# generator_DBD.net
KiCad netlist of a schematic drawn in EAGLE
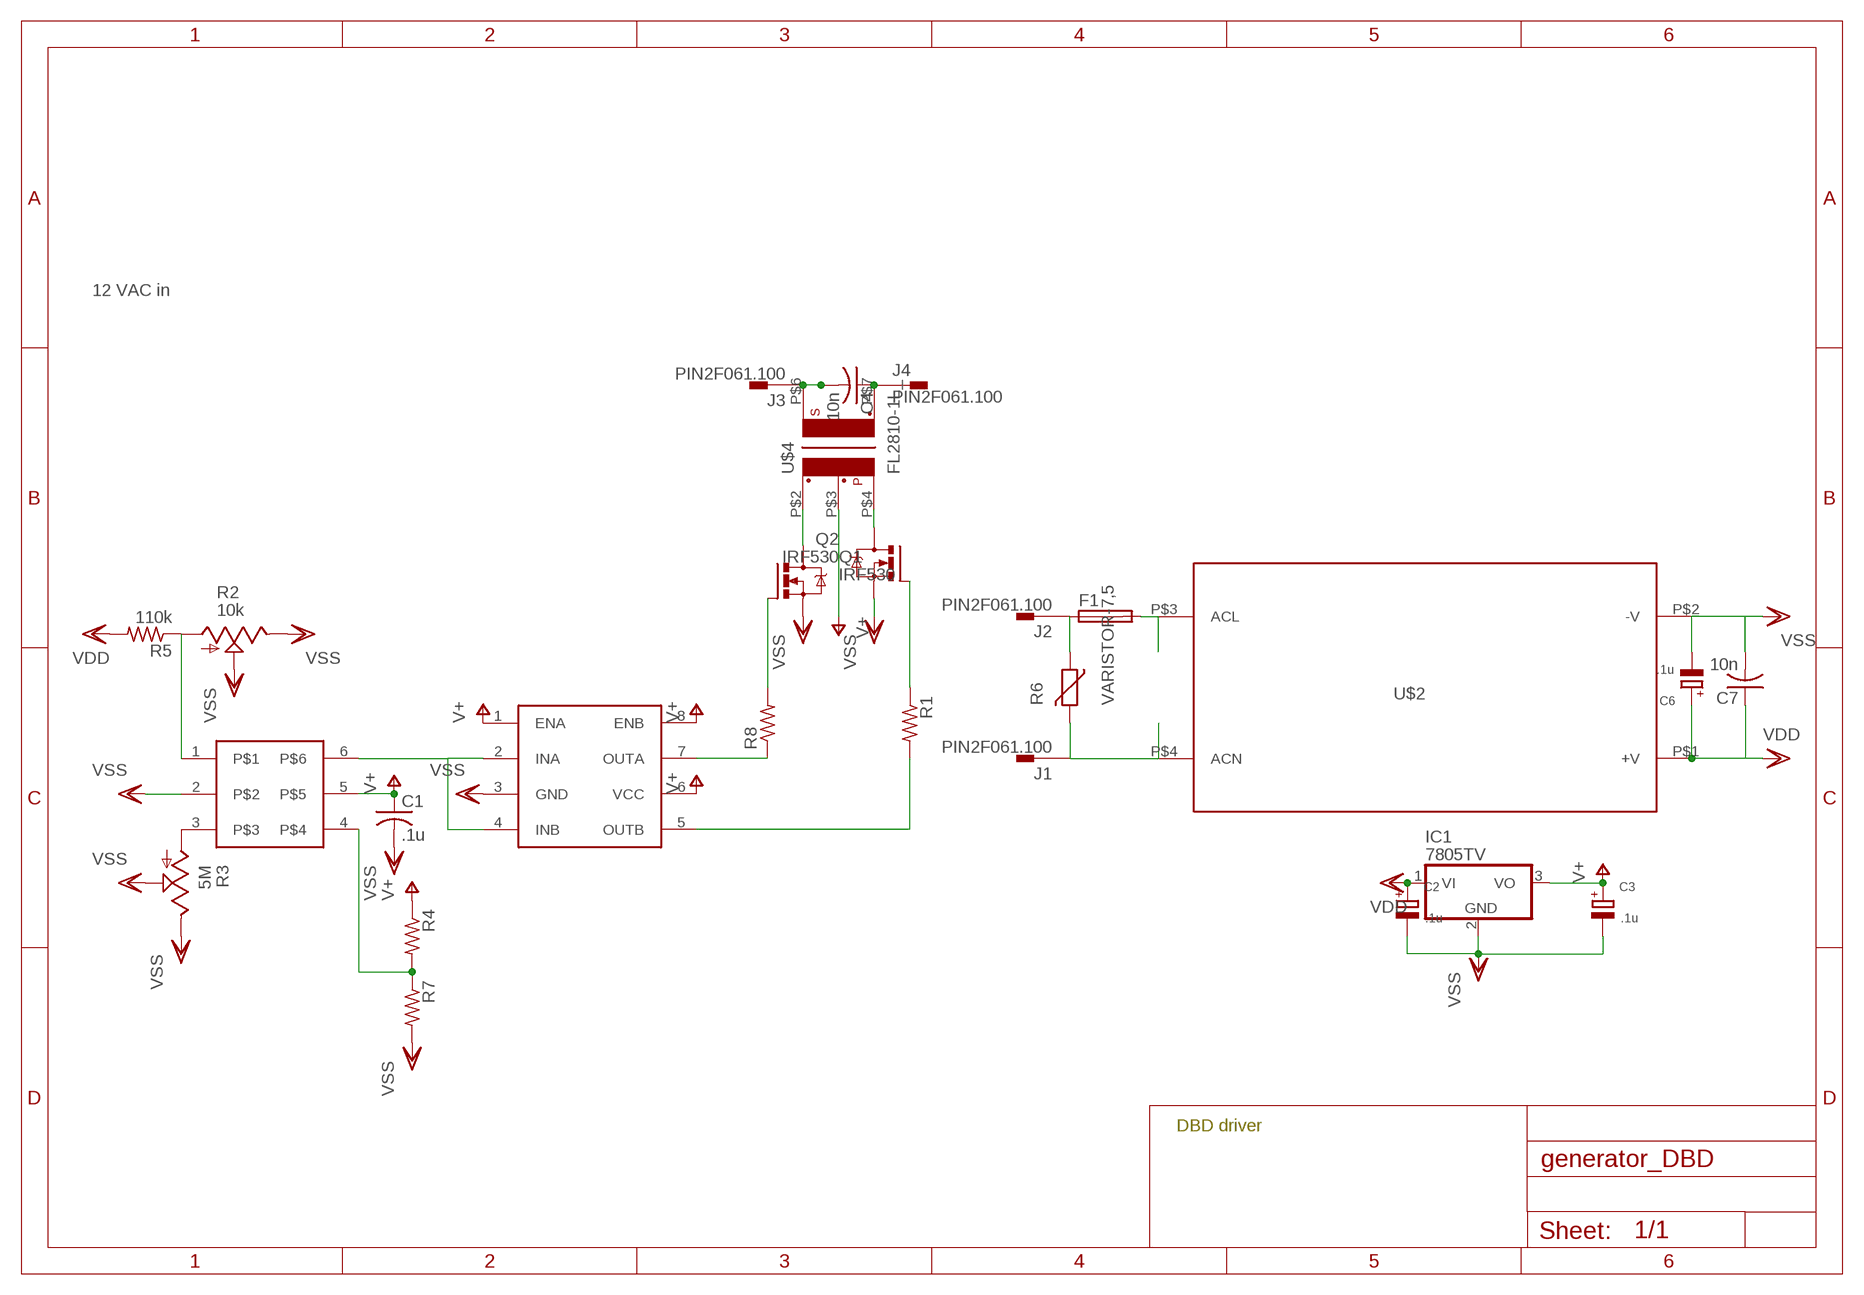
[diagram p0: schematic, sheet 1]

(export (version "E")
  (design (tool "Eeschema 10.0.6"))
  (components
    (comp (ref "C1")
      (value ".1u")
      (footprint "eagle-import:C075-042X103")
      (libsource (lib "eagle-import") (part "C-US075-042X103"))
    )
    (comp (ref "C2")
      (value ".1u")
      (footprint "eagle-import:E5-8,5")
      (libsource (lib "eagle-import") (part "CPOL-EUE5-8.5"))
    )
    (comp (ref "C3")
      (value ".1u")
      (footprint "eagle-import:E5-8,5")
      (libsource (lib "eagle-import") (part "CPOL-EUE5-8.5"))
    )
    (comp (ref "C4")
      (value "10n")
      (footprint "eagle-import:C075-042X103")
      (libsource (lib "eagle-import") (part "C-US075-042X103"))
    )
    (comp (ref "C6")
      (value ".1u")
      (footprint "eagle-import:E5-8,5")
      (libsource (lib "eagle-import") (part "CPOL-EUE5-8.5"))
    )
    (comp (ref "C7")
      (value "10n")
      (footprint "eagle-import:C075-042X103")
      (libsource (lib "eagle-import") (part "C-US075-042X103"))
    )
    (comp (ref "F1")
      (value "SH25")
      (footprint "eagle-import:SH25")
      (fields (field (name "MF") "SCHURTER") (field (name "MPN") "0031.8211"))
      (libsource (lib "eagle-import") (part "SH25"))
    )
    (comp (ref "IC1")
      (value "7805TV")
      (footprint "eagle-import:TO220V")
      (libsource (lib "eagle-import") (part "78TV05"))
    )
    (comp (ref "J1")
      (value "PIN2F061.100")
      (footprint "eagle-import:F061.100")
      (libsource (lib "eagle-import") (part "PIN2F061.100"))
    )
    (comp (ref "J2")
      (value "PIN2F061.100")
      (footprint "eagle-import:F061.100")
      (libsource (lib "eagle-import") (part "PIN2F061.100"))
    )
    (comp (ref "J3")
      (value "PIN2F061.100")
      (footprint "eagle-import:F061.100")
      (libsource (lib "eagle-import") (part "PIN2F061.100"))
    )
    (comp (ref "J4")
      (value "PIN2F061.100")
      (footprint "eagle-import:F061.100")
      (libsource (lib "eagle-import") (part "PIN2F061.100"))
    )
    (comp (ref "Q1")
      (value "IRF530")
      (footprint "eagle-import:TO220BV")
      (libsource (lib "eagle-import") (part "IRF530"))
    )
    (comp (ref "Q2")
      (value "IRF530")
      (footprint "eagle-import:TO220BV")
      (libsource (lib "eagle-import") (part "IRF530"))
    )
    (comp (ref "R1")
      (value "R-US_0207/10")
      (footprint "eagle-import:0207_10")
      (libsource (lib "eagle-import") (part "R-US_0207/10"))
    )
    (comp (ref "R2")
      (value "10k")
      (footprint "eagle-import:PT-SPIN-2")
      (libsource (lib "eagle-import") (part "TRIM_US-PT-SPIN"))
    )
    (comp (ref "R3")
      (value "5M")
      (footprint "eagle-import:PT-SPIN-2")
      (libsource (lib "eagle-import") (part "TRIM_US-PTSPIN"))
    )
    (comp (ref "R4")
      (value "R-US_0207/10")
      (footprint "eagle-import:0207_10")
      (libsource (lib "eagle-import") (part "R-US_0207/10"))
    )
    (comp (ref "R5")
      (value "110k")
      (footprint "eagle-import:0207_10")
      (libsource (lib "eagle-import") (part "R-US_0207/10"))
    )
    (comp (ref "R6")
      (value "VARISTOR-7,5")
      (footprint "eagle-import:R-7,5")
      (libsource (lib "eagle-import") (part "VARISTOR-7,5"))
    )
    (comp (ref "R7")
      (value "R-US_0207/10")
      (footprint "eagle-import:0207_10")
      (libsource (lib "eagle-import") (part "R-US_0207/10"))
    )
    (comp (ref "R8")
      (value "R-US_0207/15")
      (footprint "eagle-import:0207_15")
      (libsource (lib "eagle-import") (part "R-US_0207/15"))
    )
    (comp (ref "U$1")
      (value "UCC27425")
      (footprint "eagle-import:DIL08")
      (libsource (lib "eagle-import") (part "UCC27425"))
    )
    (comp (ref "U$2")
      (value "IRM-60-12")
      (footprint "eagle-import:IRM-60-12")
      (libsource (lib "eagle-import") (part "IRM-60-12"))
    )
    (comp (ref "U$3")
      (value "LTC6992SMD")
      (footprint "eagle-import:SOT23-6")
      (libsource (lib "eagle-import") (part "LTC6992SMD"))
    )
    (comp (ref "U$4")
      (value "FL2810-1L_")
      (footprint "eagle-import:4")
      (libsource (lib "eagle-import") (part "FL2810-1L_"))
    )
  )
  (nets
    (net (code "1") (name "Net-(F1-Pad1)") (class "Default")
      (node (ref "F1") (pin "1") (pinfunction "1_1") (pintype "passive"))
      (node (ref "J2") (pin "A1") (pinfunction "1_A1") (pintype "passive"))
      (node (ref "J2") (pin "A2") (pinfunction "1_A2") (pintype "passive"))
      (node (ref "R6") (pin "1") (pinfunction "1_1") (pintype "passive"))
    )
    (net (code "2") (name "Net-(Q1-PadG)") (class "Default")
      (node (ref "Q1") (pin "G") (pinfunction "G_G") (pintype "passive"))
      (node (ref "R8") (pin "2") (pinfunction "2_2") (pintype "passive"))
    )
    (net (code "3") (name "Net-(Q2-PadG)") (class "Default")
      (node (ref "Q2") (pin "G") (pinfunction "G_G") (pintype "passive"))
      (node (ref "R1") (pin "1") (pinfunction "1_1") (pintype "passive"))
    )
    (net (code "4") (name "Net-(U$1-INA)") (class "Default")
      (node (ref "U$1") (pin "2") (pinfunction "INA_2") (pintype "bidirectional"))
      (node (ref "U$1") (pin "4") (pinfunction "INB_4") (pintype "bidirectional"))
      (node (ref "U$3") (pin "6") (pinfunction "P$6_6") (pintype "bidirectional"))
    )
    (net (code "5") (name "Net-(U$1-OUTA)") (class "Default")
      (node (ref "R8") (pin "1") (pinfunction "1_1") (pintype "passive"))
      (node (ref "U$1") (pin "7") (pinfunction "OUTA_7") (pintype "bidirectional"))
    )
    (net (code "6") (name "Net-(U$1-OUTB)") (class "Default")
      (node (ref "R1") (pin "2") (pinfunction "2_2") (pintype "passive"))
      (node (ref "U$1") (pin "5") (pinfunction "OUTB_5") (pintype "bidirectional"))
    )
    (net (code "7") (name "Net-(U$2-ACL)") (class "Default")
      (node (ref "F1") (pin "2") (pinfunction "2_2") (pintype "passive"))
      (node (ref "U$2") (pin "P$3") (pinfunction "ACL_P$3") (pintype "bidirectional"))
    )
    (net (code "8") (name "Net-(U$2-ACN)") (class "Default")
      (node (ref "J1") (pin "A1") (pinfunction "1_A1") (pintype "passive"))
      (node (ref "J1") (pin "A2") (pinfunction "1_A2") (pintype "passive"))
      (node (ref "R6") (pin "2") (pinfunction "2_2") (pintype "passive"))
      (node (ref "U$2") (pin "P$4") (pinfunction "ACN_P$4") (pintype "bidirectional"))
    )
    (net (code "9") (name "Net-(U$3-P$1)") (class "Default")
      (node (ref "R2") (pin "A") (pinfunction "A_A") (pintype "passive"))
      (node (ref "R5") (pin "1") (pinfunction "1_1") (pintype "passive"))
      (node (ref "U$3") (pin "1") (pinfunction "P$1_1") (pintype "bidirectional"))
    )
    (net (code "10") (name "Net-(U$3-P$3)") (class "Default")
      (node (ref "R3") (pin "A") (pinfunction "A_A") (pintype "passive"))
      (node (ref "U$3") (pin "3") (pinfunction "P$3_3") (pintype "bidirectional"))
    )
    (net (code "11") (name "Net-(U$3-P$4)") (class "Default")
      (node (ref "R4") (pin "2") (pinfunction "2_2") (pintype "passive"))
      (node (ref "R7") (pin "1") (pinfunction "1_1") (pintype "passive"))
      (node (ref "U$3") (pin "4") (pinfunction "P$4_4") (pintype "bidirectional"))
    )
    (net (code "12") (name "Net-(U$4-1)") (class "Default")
      (node (ref "Q1") (pin "D") (pinfunction "D_D") (pintype "passive"))
      (node (ref "U$4") (pin "P$2") (pinfunction "1_P$2") (pintype "passive"))
    )
    (net (code "13") (name "Net-(U$4-3)") (class "Default")
      (node (ref "Q2") (pin "D") (pinfunction "D_D") (pintype "passive"))
      (node (ref "U$4") (pin "P$4") (pinfunction "3_P$4") (pintype "passive"))
    )
    (net (code "14") (name "Net-(U$4-4)") (class "Default")
      (node (ref "C4") (pin "1") (pinfunction "1_1") (pintype "passive"))
      (node (ref "J4") (pin "A1") (pinfunction "1_A1") (pintype "passive"))
      (node (ref "J4") (pin "A2") (pinfunction "1_A2") (pintype "passive"))
      (node (ref "U$4") (pin "P$7") (pinfunction "4_P$7") (pintype "passive"))
    )
    (net (code "15") (name "Net-(U$4-6)") (class "Default")
      (node (ref "C4") (pin "2") (pinfunction "2_2") (pintype "passive"))
      (node (ref "J3") (pin "A1") (pinfunction "1_A1") (pintype "passive"))
      (node (ref "J3") (pin "A2") (pinfunction "1_A2") (pintype "passive"))
      (node (ref "U$4") (pin "P$6") (pinfunction "6_P$6") (pintype "passive"))
    )
    (net (code "16") (name "V+") (class "Default")
      (node (ref "C1") (pin "1") (pinfunction "1_1") (pintype "passive"))
      (node (ref "C3") (pin "+") (pinfunction "+_+") (pintype "passive"))
      (node (ref "IC1") (pin "3") (pinfunction "VO_3") (pintype "passive"))
      (node (ref "R4") (pin "1") (pinfunction "1_1") (pintype "passive"))
      (node (ref "U$1") (pin "1") (pinfunction "ENA_1") (pintype "bidirectional"))
      (node (ref "U$1") (pin "6") (pinfunction "VCC_6") (pintype "bidirectional"))
      (node (ref "U$1") (pin "8") (pinfunction "ENB_8") (pintype "bidirectional"))
      (node (ref "U$3") (pin "5") (pinfunction "P$5_5") (pintype "bidirectional"))
      (node (ref "U$4") (pin "P$3") (pinfunction "2_P$3") (pintype "passive"))
    )
    (net (code "17") (name "VDD") (class "Default")
      (node (ref "C2") (pin "+") (pinfunction "+_+") (pintype "passive"))
      (node (ref "C6") (pin "+") (pinfunction "+_+") (pintype "passive"))
      (node (ref "C7") (pin "1") (pinfunction "1_1") (pintype "passive"))
      (node (ref "IC1") (pin "1") (pinfunction "VI_1") (pintype "input"))
      (node (ref "R5") (pin "2") (pinfunction "2_2") (pintype "passive"))
      (node (ref "U$2") (pin "P$1") (pinfunction "+V_P$1") (pintype "bidirectional"))
    )
    (net (code "18") (name "VSS") (class "Default")
      (node (ref "C1") (pin "2") (pinfunction "2_2") (pintype "passive"))
      (node (ref "C2") (pin "-") (pinfunction "-_-") (pintype "passive"))
      (node (ref "C3") (pin "-") (pinfunction "-_-") (pintype "passive"))
      (node (ref "C6") (pin "-") (pinfunction "-_-") (pintype "passive"))
      (node (ref "C7") (pin "2") (pinfunction "2_2") (pintype "passive"))
      (node (ref "IC1") (pin "2") (pinfunction "GND_2") (pintype "passive"))
      (node (ref "Q1") (pin "S") (pinfunction "S_S") (pintype "passive"))
      (node (ref "Q2") (pin "S") (pinfunction "S_S") (pintype "passive"))
      (node (ref "R2") (pin "E") (pinfunction "E_E") (pintype "passive"))
      (node (ref "R2") (pin "S") (pinfunction "S_S") (pintype "passive"))
      (node (ref "R3") (pin "E") (pinfunction "E_E") (pintype "passive"))
      (node (ref "R3") (pin "S") (pinfunction "S_S") (pintype "passive"))
      (node (ref "R7") (pin "2") (pinfunction "2_2") (pintype "passive"))
      (node (ref "U$1") (pin "3") (pinfunction "GND_3") (pintype "bidirectional"))
      (node (ref "U$2") (pin "P$2") (pinfunction "-V_P$2") (pintype "bidirectional"))
      (node (ref "U$3") (pin "2") (pinfunction "P$2_2") (pintype "bidirectional"))
    )
  )
)
